# Calefactor.net
KiCad netlist of a schematic drawn in Altium Designer
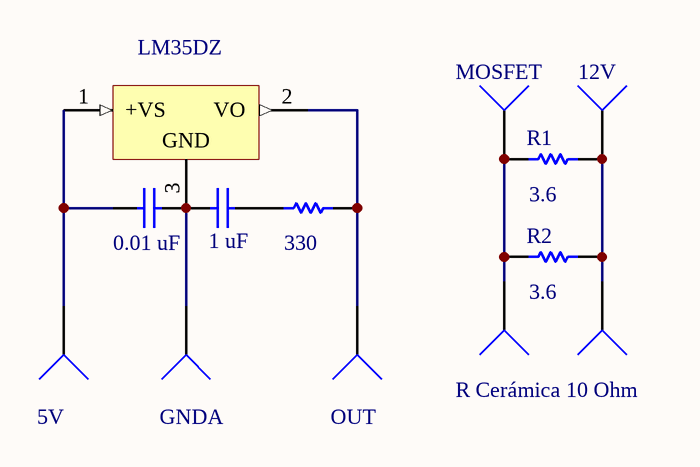
[diagram p0: Calefactor.SchDoc]

(export (version "E")
  (design (tool "Eeschema 10.0.6"))
  (components
    (comp (ref "C1")
      (value "0.01 uF")
      (footprint "KEMT-C315-THT-2")
      (description "Capacitor, Ceramic, 1000 pF, +/-10 %, 100 V, X7R, -55 to 125 degC, 2-Pin THD, RoHS, Bulk")
      (libsource (lib "Altium Content Vault") (part "CAP-NP-2"))
    )
    (comp (ref "C2")
      (value "1 uF")
      (footprint "KEMT-C315-THT-2")
      (description "Capacitor, Ceramic, 1000 pF, +/-10 %, 100 V, X7R, -55 to 125 degC, 2-Pin THD, RoHS, Bulk")
      (libsource (lib "Altium Content Vault") (part "CAP-NP-2"))
    )
    (comp (ref "J1")
      (value "12V")
      (footprint "PIN1")
      (description "Socket")
      (fields (field (name "PUBLISHER") "Altium Limited"))
      (libsource (lib "Miscellaneous Connectors") (part "Socket"))
    )
    (comp (ref "J2")
      (value "MOSFET")
      (footprint "PIN1")
      (description "Socket")
      (fields (field (name "PUBLISHER") "Altium Limited"))
      (libsource (lib "Miscellaneous Connectors") (part "Socket"))
    )
    (comp (ref "J3")
      (value "12 V")
      (footprint "PIN1")
      (description "Socket")
      (fields (field (name "PUBLISHER") "Altium Limited"))
      (libsource (lib "Miscellaneous Connectors") (part "Socket"))
    )
    (comp (ref "J4")
      (value "MOSFET")
      (footprint "PIN1")
      (description "Socket")
      (fields (field (name "PUBLISHER") "Altium Limited"))
      (libsource (lib "Miscellaneous Connectors") (part "Socket"))
    )
    (comp (ref "J5")
      (value "GNDA")
      (footprint "PIN1")
      (description "Socket")
      (fields (field (name "PUBLISHER") "Altium Limited"))
      (libsource (lib "Miscellaneous Connectors") (part "Socket"))
    )
    (comp (ref "J6")
      (value "OUT")
      (footprint "PIN1")
      (description "Socket")
      (fields (field (name "PUBLISHER") "Altium Limited"))
      (libsource (lib "Miscellaneous Connectors") (part "Socket"))
    )
    (comp (ref "J7")
      (value "5V")
      (footprint "PIN1")
      (description "Socket")
      (fields (field (name "PUBLISHER") "Altium Limited"))
      (libsource (lib "Miscellaneous Connectors") (part "Socket"))
    )
    (comp (ref "R1")
      (value "3.6")
      (footprint "AXIAL-0.3")
      (description "Resistor")
      (fields (field (name "Comment") "Res1") (field (name "PUBLISHER") "Altium Limited"))
      (libsource (lib "Miscellaneous Devices") (part "Res1"))
    )
    (comp (ref "R2")
      (value "3.6")
      (footprint "AXIAL-0.3")
      (description "Resistor")
      (fields (field (name "Comment") "Res1") (field (name "PUBLISHER") "Altium Limited"))
      (libsource (lib "Miscellaneous Devices") (part "Res1"))
    )
    (comp (ref "R3")
      (value "330")
      (footprint "AXIAL-0.3")
      (description "Resistor")
      (fields (field (name "Comment") "Res2") (field (name "PUBLISHER") "Altium Limited"))
      (libsource (lib "Miscellaneous Devices") (part "Res1"))
    )
    (comp (ref "U1")
      (value "LM35DZ")
      (footprint "Z03A")
      (description "Precision Centigrade Temperature Sensor, 3-pin TO-92")
      (fields (field (name "MANUFACTURER") "National Semiconductor"))
      (libsource (lib "Altium Content Vault") (part "SEN-TEMP-LM34AH-3"))
    )
  )
  (nets
    (net (code "1") (name "Net-(C2-Pad1)") (class "Default")
      (node (ref "C2") (pin "1") (pinfunction "1_1") (pintype "passive"))
      (node (ref "R3") (pin "1") (pinfunction "1_1") (pintype "passive"))
    )
    (net (code "2") (name "Net-(J1-Pad1)") (class "Default")
      (node (ref "J1") (pin "1") (pinfunction "1_1") (pintype "passive"))
      (node (ref "J3") (pin "1") (pinfunction "1_1") (pintype "passive"))
      (node (ref "R1") (pin "2") (pinfunction "2_2") (pintype "passive"))
      (node (ref "R2") (pin "2") (pinfunction "2_2") (pintype "passive"))
    )
    (net (code "3") (name "Net-(J2-Pad1)") (class "Default")
      (node (ref "J2") (pin "1") (pinfunction "1_1") (pintype "passive"))
      (node (ref "J4") (pin "1") (pinfunction "1_1") (pintype "passive"))
      (node (ref "R1") (pin "1") (pinfunction "1_1") (pintype "passive"))
      (node (ref "R2") (pin "1") (pinfunction "1_1") (pintype "passive"))
    )
    (net (code "4") (name "Net-(U1-+VS)") (class "Default")
      (node (ref "C1") (pin "2") (pinfunction "2_2") (pintype "passive"))
      (node (ref "J7") (pin "1") (pinfunction "1_1") (pintype "passive"))
      (node (ref "U1") (pin "1") (pinfunction "+VS_1") (pintype "input"))
    )
    (net (code "5") (name "Net-(U1-GND)") (class "Default")
      (node (ref "C1") (pin "1") (pinfunction "1_1") (pintype "passive"))
      (node (ref "C2") (pin "2") (pinfunction "2_2") (pintype "passive"))
      (node (ref "J5") (pin "1") (pinfunction "1_1") (pintype "passive"))
      (node (ref "U1") (pin "3") (pinfunction "GND_3") (pintype "power_in"))
    )
    (net (code "6") (name "Net-(U1-VO)") (class "Default")
      (node (ref "J6") (pin "1") (pinfunction "1_1") (pintype "passive"))
      (node (ref "R3") (pin "2") (pinfunction "2_2") (pintype "passive"))
      (node (ref "U1") (pin "2") (pinfunction "VO_2") (pintype "output"))
    )
  )
)
